# LED.net
KiCad netlist of a schematic drawn in EAGLE
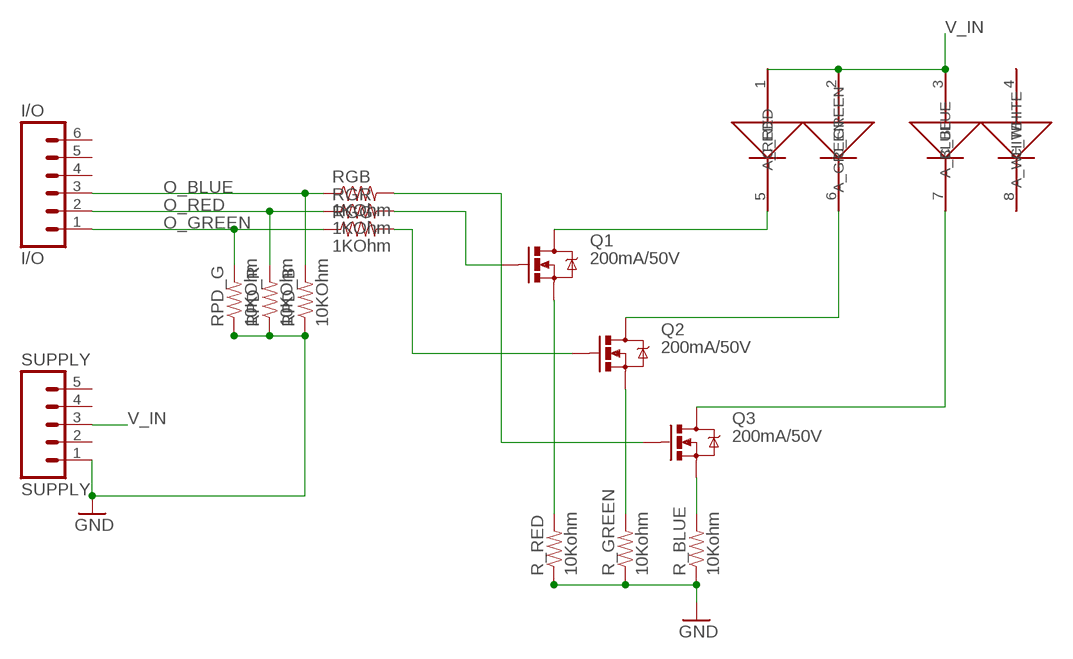
[diagram p0: schematic, sheet 1]

(export (version "E")
  (design (tool "Eeschema 10.0.6"))
  (components
    (comp (ref "I/O")
      (value "I/O")
      (footprint "eagle-import:1X06_NO_SILK")
      (libsource (lib "eagle-import") (part "M06NO_SILK_FEMALE_PTH"))
    )
    (comp (ref "Q1")
      (value "200mA/50V")
      (footprint "eagle-import:SOT23-3")
      (libsource (lib "eagle-import") (part "MOSFET-NCHANNELBSS138"))
    )
    (comp (ref "Q2")
      (value "200mA/50V")
      (footprint "eagle-import:SOT23-3")
      (libsource (lib "eagle-import") (part "MOSFET-NCHANNELBSS138"))
    )
    (comp (ref "Q3")
      (value "200mA/50V")
      (footprint "eagle-import:SOT23-3")
      (libsource (lib "eagle-import") (part "MOSFET-NCHANNELBSS138"))
    )
    (comp (ref "RGB")
      (value "1KOhm")
      (footprint "eagle-import:0805")
      (libsource (lib "eagle-import") (part "RESISTOR0805-RES"))
    )
    (comp (ref "RGG")
      (value "1KOhm")
      (footprint "eagle-import:0805")
      (libsource (lib "eagle-import") (part "RESISTOR0805-RES"))
    )
    (comp (ref "RGR")
      (value "1KOhm")
      (footprint "eagle-import:0805")
      (libsource (lib "eagle-import") (part "RESISTOR0805-RES"))
    )
    (comp (ref "RPD_B")
      (value "10KOhm")
      (footprint "eagle-import:0805")
      (libsource (lib "eagle-import") (part "RESISTOR0805-RES"))
    )
    (comp (ref "RPD_G")
      (value "10KOhm")
      (footprint "eagle-import:0805")
      (libsource (lib "eagle-import") (part "RESISTOR0805-RES"))
    )
    (comp (ref "RPD_R")
      (value "10KOhm")
      (footprint "eagle-import:0805")
      (libsource (lib "eagle-import") (part "RESISTOR0805-RES"))
    )
    (comp (ref "R_BLUE")
      (value "10Kohm")
      (footprint "eagle-import:0805")
      (libsource (lib "eagle-import") (part "RESISTOR0805-RES"))
    )
    (comp (ref "R_GREEN")
      (value "10Kohm")
      (footprint "eagle-import:0805")
      (libsource (lib "eagle-import") (part "RESISTOR0805-RES"))
    )
    (comp (ref "R_RED")
      (value "10Kohm")
      (footprint "eagle-import:0805")
      (libsource (lib "eagle-import") (part "RESISTOR0805-RES"))
    )
    (comp (ref "SUPPLY")
      (value "SUPPLY")
      (footprint "eagle-import:1X05_NO_SILK")
      (libsource (lib "eagle-import") (part "M05NO_SILK"))
    )
    (comp (ref "U$1")
      (value "CREE_MCE4CTRGBW")
      (footprint "eagle-import:CLN6A")
      (libsource (lib "eagle-import") (part "CREE_MCE4CTRGBW"))
    )
  )
  (nets
    (net (code "1") (name "/O_BLUE") (class "Default")
      (node (ref "I/O") (pin "3") (pinfunction "3_3") (pintype "passive"))
      (node (ref "RGB") (pin "1") (pinfunction "1_1") (pintype "passive"))
      (node (ref "RPD_B") (pin "2") (pinfunction "2_2") (pintype "passive"))
    )
    (net (code "2") (name "/O_GREEN") (class "Default")
      (node (ref "I/O") (pin "1") (pinfunction "1_1") (pintype "passive"))
      (node (ref "RGG") (pin "1") (pinfunction "1_1") (pintype "passive"))
      (node (ref "RPD_G") (pin "2") (pinfunction "2_2") (pintype "passive"))
    )
    (net (code "3") (name "/O_RED") (class "Default")
      (node (ref "I/O") (pin "2") (pinfunction "2_2") (pintype "passive"))
      (node (ref "RGR") (pin "1") (pinfunction "1_1") (pintype "passive"))
      (node (ref "RPD_R") (pin "2") (pinfunction "2_2") (pintype "passive"))
    )
    (net (code "4") (name "/V_IN") (class "Default")
      (node (ref "SUPPLY") (pin "3") (pinfunction "3_3") (pintype "passive"))
      (node (ref "U$1") (pin "1") (pinfunction "A_RED_1") (pintype "bidirectional"))
      (node (ref "U$1") (pin "2") (pinfunction "A_GREEN_2") (pintype "bidirectional"))
      (node (ref "U$1") (pin "3") (pinfunction "A_BLUE_3") (pintype "bidirectional"))
    )
    (net (code "5") (name "GND") (class "Default")
      (node (ref "RPD_B") (pin "1") (pinfunction "1_1") (pintype "passive"))
      (node (ref "RPD_G") (pin "1") (pinfunction "1_1") (pintype "passive"))
      (node (ref "RPD_R") (pin "1") (pinfunction "1_1") (pintype "passive"))
      (node (ref "R_BLUE") (pin "1") (pinfunction "1_1") (pintype "passive"))
      (node (ref "R_GREEN") (pin "1") (pinfunction "1_1") (pintype "passive"))
      (node (ref "R_RED") (pin "1") (pinfunction "1_1") (pintype "passive"))
      (node (ref "SUPPLY") (pin "1") (pinfunction "1_1") (pintype "passive"))
    )
    (net (code "6") (name "Net-(Q1-D)") (class "Default")
      (node (ref "Q1") (pin "3") (pinfunction "D_3") (pintype "passive"))
      (node (ref "U$1") (pin "5") (pinfunction "C_RED_5") (pintype "bidirectional"))
    )
    (net (code "7") (name "Net-(Q1-G)") (class "Default")
      (node (ref "Q1") (pin "1") (pinfunction "G_1") (pintype "passive"))
      (node (ref "RGR") (pin "2") (pinfunction "2_2") (pintype "passive"))
    )
    (net (code "8") (name "Net-(Q1-S)") (class "Default")
      (node (ref "Q1") (pin "2") (pinfunction "S_2") (pintype "passive"))
      (node (ref "R_RED") (pin "2") (pinfunction "2_2") (pintype "passive"))
    )
    (net (code "9") (name "Net-(Q2-D)") (class "Default")
      (node (ref "Q2") (pin "3") (pinfunction "D_3") (pintype "passive"))
      (node (ref "U$1") (pin "6") (pinfunction "C_GREEN_6") (pintype "bidirectional"))
    )
    (net (code "10") (name "Net-(Q2-G)") (class "Default")
      (node (ref "Q2") (pin "1") (pinfunction "G_1") (pintype "passive"))
      (node (ref "RGG") (pin "2") (pinfunction "2_2") (pintype "passive"))
    )
    (net (code "11") (name "Net-(Q2-S)") (class "Default")
      (node (ref "Q2") (pin "2") (pinfunction "S_2") (pintype "passive"))
      (node (ref "R_GREEN") (pin "2") (pinfunction "2_2") (pintype "passive"))
    )
    (net (code "12") (name "Net-(Q3-D)") (class "Default")
      (node (ref "Q3") (pin "3") (pinfunction "D_3") (pintype "passive"))
      (node (ref "U$1") (pin "7") (pinfunction "C_BLUE_7") (pintype "bidirectional"))
    )
    (net (code "13") (name "Net-(Q3-G)") (class "Default")
      (node (ref "Q3") (pin "1") (pinfunction "G_1") (pintype "passive"))
      (node (ref "RGB") (pin "2") (pinfunction "2_2") (pintype "passive"))
    )
    (net (code "14") (name "Net-(Q3-S)") (class "Default")
      (node (ref "Q3") (pin "2") (pinfunction "S_2") (pintype "passive"))
      (node (ref "R_BLUE") (pin "2") (pinfunction "2_2") (pintype "passive"))
    )
    (net (code "15") (name "unconnected-(I/O-Pad4)") (class "Default")
      (node (ref "I/O") (pin "4") (pinfunction "4_4") (pintype "passive"))
    )
    (net (code "16") (name "unconnected-(I/O-Pad5)") (class "Default")
      (node (ref "I/O") (pin "5") (pinfunction "5_5") (pintype "passive"))
    )
    (net (code "17") (name "unconnected-(I/O-Pad6)") (class "Default")
      (node (ref "I/O") (pin "6") (pinfunction "6_6") (pintype "passive"))
    )
    (net (code "18") (name "unconnected-(SUPPLY-Pad2)") (class "Default")
      (node (ref "SUPPLY") (pin "2") (pinfunction "2_2") (pintype "passive"))
    )
    (net (code "19") (name "unconnected-(SUPPLY-Pad4)") (class "Default")
      (node (ref "SUPPLY") (pin "4") (pinfunction "4_4") (pintype "passive"))
    )
    (net (code "20") (name "unconnected-(SUPPLY-Pad5)") (class "Default")
      (node (ref "SUPPLY") (pin "5") (pinfunction "5_5") (pintype "passive"))
    )
    (net (code "21") (name "unconnected-(U$1-A_WHITE-Pad4)") (class "Default")
      (node (ref "U$1") (pin "4") (pinfunction "A_WHITE_4") (pintype "bidirectional"))
    )
    (net (code "22") (name "unconnected-(U$1-C_WHITE-Pad8)") (class "Default")
      (node (ref "U$1") (pin "8") (pinfunction "C_WHITE_8") (pintype "bidirectional"))
    )
  )
)
